# HDMI.net
KiCad netlist of a schematic drawn in Altium Designer
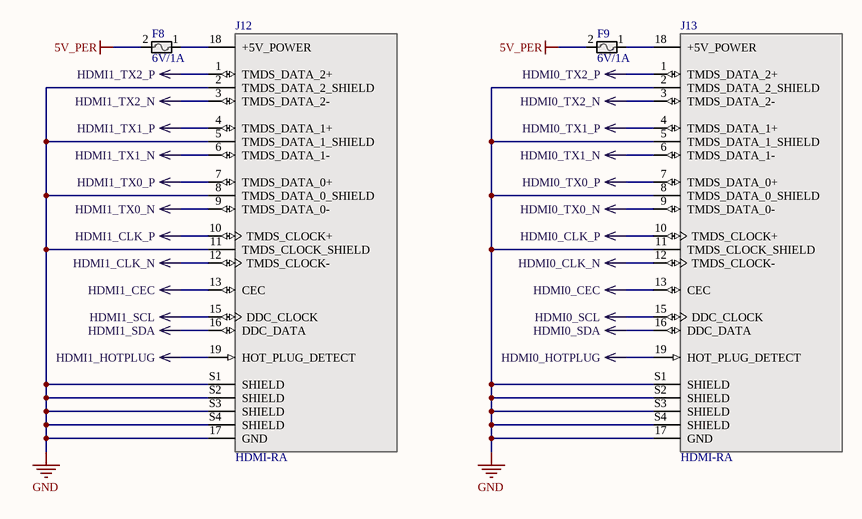
[diagram p0: HDMI.SchDoc]

(export (version "E")
  (design (tool "Eeschema 10.0.6"))
  (components
    (comp (ref "F8")
      (value "6V/1A")
      (footprint "0805")
      (description "Polymeric PTC Resettable Fuse 6V 1 A Ih Surface Mount 0805 (2012 Metric), Concave")
      (fields (field (name "MANUFACTURER") "Bel") (field (name "MANUFACTURER PART NUMBER") "0ZCK0100FF2E"))
      (libsource (lib "Regulators") (part "0ZCK0100FF2E"))
    )
    (comp (ref "F9")
      (value "6V/1A")
      (footprint "0805")
      (description "Polymeric PTC Resettable Fuse 6V 1 A Ih Surface Mount 0805 (2012 Metric), Concave")
      (fields (field (name "MANUFACTURER") "Bel") (field (name "MANUFACTURER PART NUMBER") "0ZCK0100FF2E"))
      (libsource (lib "Regulators") (part "0ZCK0100FF2E"))
    )
    (comp (ref "J12")
      (value "HDMI-RA")
      (footprint "CUI_HD01-19-RA-TH")
      (description "HDMI 2.1, Receptacle Connector, 19 Position, Through Hole, Vertical, Right Angle, Tray Packaging")
      (fields (field (name "MF") "CUI Devices") (field (name "DIGI-KEY_PART_NUMBER") "2223-HD01-19-RA-TH-ND"))
      (libsource (lib "Connectors") (part "HD01-19-RA-TH"))
    )
    (comp (ref "J13")
      (value "HDMI-RA")
      (footprint "CUI_HD01-19-RA-TH")
      (description "HDMI 2.1, Receptacle Connector, 19 Position, Through Hole, Vertical, Right Angle, Tray Packaging")
      (fields (field (name "MF") "CUI Devices") (field (name "DIGI-KEY_PART_NUMBER") "2223-HD01-19-RA-TH-ND"))
      (libsource (lib "Connectors") (part "HD01-19-RA-TH"))
    )
  )
  (nets
    (net (code "1") (name "5V_PER") (class "Default")
      (node (ref "F8") (pin "2") (pinfunction "2_2") (pintype "passive"))
      (node (ref "F9") (pin "2") (pinfunction "2_2") (pintype "passive"))
    )
    (net (code "2") (name "GND") (class "Default")
      (node (ref "J12") (pin "11") (pinfunction "TMDS_CLOCK_SHIELD_11") (pintype "passive"))
      (node (ref "J12") (pin "17") (pinfunction "GND_17") (pintype "power_in"))
      (node (ref "J12") (pin "2") (pinfunction "TMDS_DATA_2_SHIELD_2") (pintype "passive"))
      (node (ref "J12") (pin "5") (pinfunction "TMDS_DATA_1_SHIELD_5") (pintype "passive"))
      (node (ref "J12") (pin "8") (pinfunction "TMDS_DATA_0_SHIELD_8") (pintype "passive"))
      (node (ref "J12") (pin "S1") (pinfunction "SHIELD_S1") (pintype "passive"))
      (node (ref "J12") (pin "S2") (pinfunction "SHIELD_S2") (pintype "passive"))
      (node (ref "J12") (pin "S3") (pinfunction "SHIELD_S3") (pintype "passive"))
      (node (ref "J12") (pin "S4") (pinfunction "SHIELD_S4") (pintype "passive"))
      (node (ref "J13") (pin "11") (pinfunction "TMDS_CLOCK_SHIELD_11") (pintype "passive"))
      (node (ref "J13") (pin "17") (pinfunction "GND_17") (pintype "power_in"))
      (node (ref "J13") (pin "2") (pinfunction "TMDS_DATA_2_SHIELD_2") (pintype "passive"))
      (node (ref "J13") (pin "5") (pinfunction "TMDS_DATA_1_SHIELD_5") (pintype "passive"))
      (node (ref "J13") (pin "8") (pinfunction "TMDS_DATA_0_SHIELD_8") (pintype "passive"))
      (node (ref "J13") (pin "S1") (pinfunction "SHIELD_S1") (pintype "passive"))
      (node (ref "J13") (pin "S2") (pinfunction "SHIELD_S2") (pintype "passive"))
      (node (ref "J13") (pin "S3") (pinfunction "SHIELD_S3") (pintype "passive"))
      (node (ref "J13") (pin "S4") (pinfunction "SHIELD_S4") (pintype "passive"))
    )
    (net (code "3") (name "HDMI0_CEC") (class "Default")
      (node (ref "J13") (pin "13") (pinfunction "CEC_13") (pintype "bidirectional"))
    )
    (net (code "4") (name "HDMI0_CLK_N") (class "Default")
      (node (ref "J13") (pin "12") (pinfunction "TMDS_CLOCK-_12") (pintype "bidirectional"))
    )
    (net (code "5") (name "HDMI0_CLK_P") (class "Default")
      (node (ref "J13") (pin "10") (pinfunction "TMDS_CLOCK+_10") (pintype "bidirectional"))
    )
    (net (code "6") (name "HDMI0_HOTPLUG") (class "Default")
      (node (ref "J13") (pin "19") (pinfunction "HOT_PLUG_DETECT_19") (pintype "input"))
    )
    (net (code "7") (name "HDMI0_SCL") (class "Default")
      (node (ref "J13") (pin "15") (pinfunction "DDC_CLOCK_15") (pintype "bidirectional"))
    )
    (net (code "8") (name "HDMI0_SDA") (class "Default")
      (node (ref "J13") (pin "16") (pinfunction "DDC_DATA_16") (pintype "bidirectional"))
    )
    (net (code "9") (name "HDMI0_TX0_N") (class "Default")
      (node (ref "J13") (pin "9") (pinfunction "TMDS_DATA_0-_9") (pintype "bidirectional"))
    )
    (net (code "10") (name "HDMI0_TX0_P") (class "Default")
      (node (ref "J13") (pin "7") (pinfunction "TMDS_DATA_0+_7") (pintype "bidirectional"))
    )
    (net (code "11") (name "HDMI0_TX1_N") (class "Default")
      (node (ref "J13") (pin "6") (pinfunction "TMDS_DATA_1-_6") (pintype "bidirectional"))
    )
    (net (code "12") (name "HDMI0_TX1_P") (class "Default")
      (node (ref "J13") (pin "4") (pinfunction "TMDS_DATA_1+_4") (pintype "bidirectional"))
    )
    (net (code "13") (name "HDMI0_TX2_N") (class "Default")
      (node (ref "J13") (pin "3") (pinfunction "TMDS_DATA_2-_3") (pintype "bidirectional"))
    )
    (net (code "14") (name "HDMI0_TX2_P") (class "Default")
      (node (ref "J13") (pin "1") (pinfunction "TMDS_DATA_2+_1") (pintype "bidirectional"))
    )
    (net (code "15") (name "HDMI1_CEC") (class "Default")
      (node (ref "J12") (pin "13") (pinfunction "CEC_13") (pintype "bidirectional"))
    )
    (net (code "16") (name "HDMI1_CLK_N") (class "Default")
      (node (ref "J12") (pin "12") (pinfunction "TMDS_CLOCK-_12") (pintype "bidirectional"))
    )
    (net (code "17") (name "HDMI1_CLK_P") (class "Default")
      (node (ref "J12") (pin "10") (pinfunction "TMDS_CLOCK+_10") (pintype "bidirectional"))
    )
    (net (code "18") (name "HDMI1_HOTPLUG") (class "Default")
      (node (ref "J12") (pin "19") (pinfunction "HOT_PLUG_DETECT_19") (pintype "input"))
    )
    (net (code "19") (name "HDMI1_SCL") (class "Default")
      (node (ref "J12") (pin "15") (pinfunction "DDC_CLOCK_15") (pintype "bidirectional"))
    )
    (net (code "20") (name "HDMI1_SDA") (class "Default")
      (node (ref "J12") (pin "16") (pinfunction "DDC_DATA_16") (pintype "bidirectional"))
    )
    (net (code "21") (name "HDMI1_TX0_N") (class "Default")
      (node (ref "J12") (pin "9") (pinfunction "TMDS_DATA_0-_9") (pintype "bidirectional"))
    )
    (net (code "22") (name "HDMI1_TX0_P") (class "Default")
      (node (ref "J12") (pin "7") (pinfunction "TMDS_DATA_0+_7") (pintype "bidirectional"))
    )
    (net (code "23") (name "HDMI1_TX1_N") (class "Default")
      (node (ref "J12") (pin "6") (pinfunction "TMDS_DATA_1-_6") (pintype "bidirectional"))
    )
    (net (code "24") (name "HDMI1_TX1_P") (class "Default")
      (node (ref "J12") (pin "4") (pinfunction "TMDS_DATA_1+_4") (pintype "bidirectional"))
    )
    (net (code "25") (name "HDMI1_TX2_N") (class "Default")
      (node (ref "J12") (pin "3") (pinfunction "TMDS_DATA_2-_3") (pintype "bidirectional"))
    )
    (net (code "26") (name "HDMI1_TX2_P") (class "Default")
      (node (ref "J12") (pin "1") (pinfunction "TMDS_DATA_2+_1") (pintype "bidirectional"))
    )
    (net (code "27") (name "Net-(J12-+5V_POWER)") (class "Default")
      (node (ref "F8") (pin "1") (pinfunction "1_1") (pintype "passive"))
      (node (ref "J12") (pin "18") (pinfunction "+5V_POWER_18") (pintype "power_in"))
    )
    (net (code "28") (name "Net-(J13-+5V_POWER)") (class "Default")
      (node (ref "F9") (pin "1") (pinfunction "1_1") (pintype "passive"))
      (node (ref "J13") (pin "18") (pinfunction "+5V_POWER_18") (pintype "power_in"))
    )
  )
)
